# OVC3860_Bluetooth_Receiver.net
KiCad netlist of a schematic drawn in EAGLE
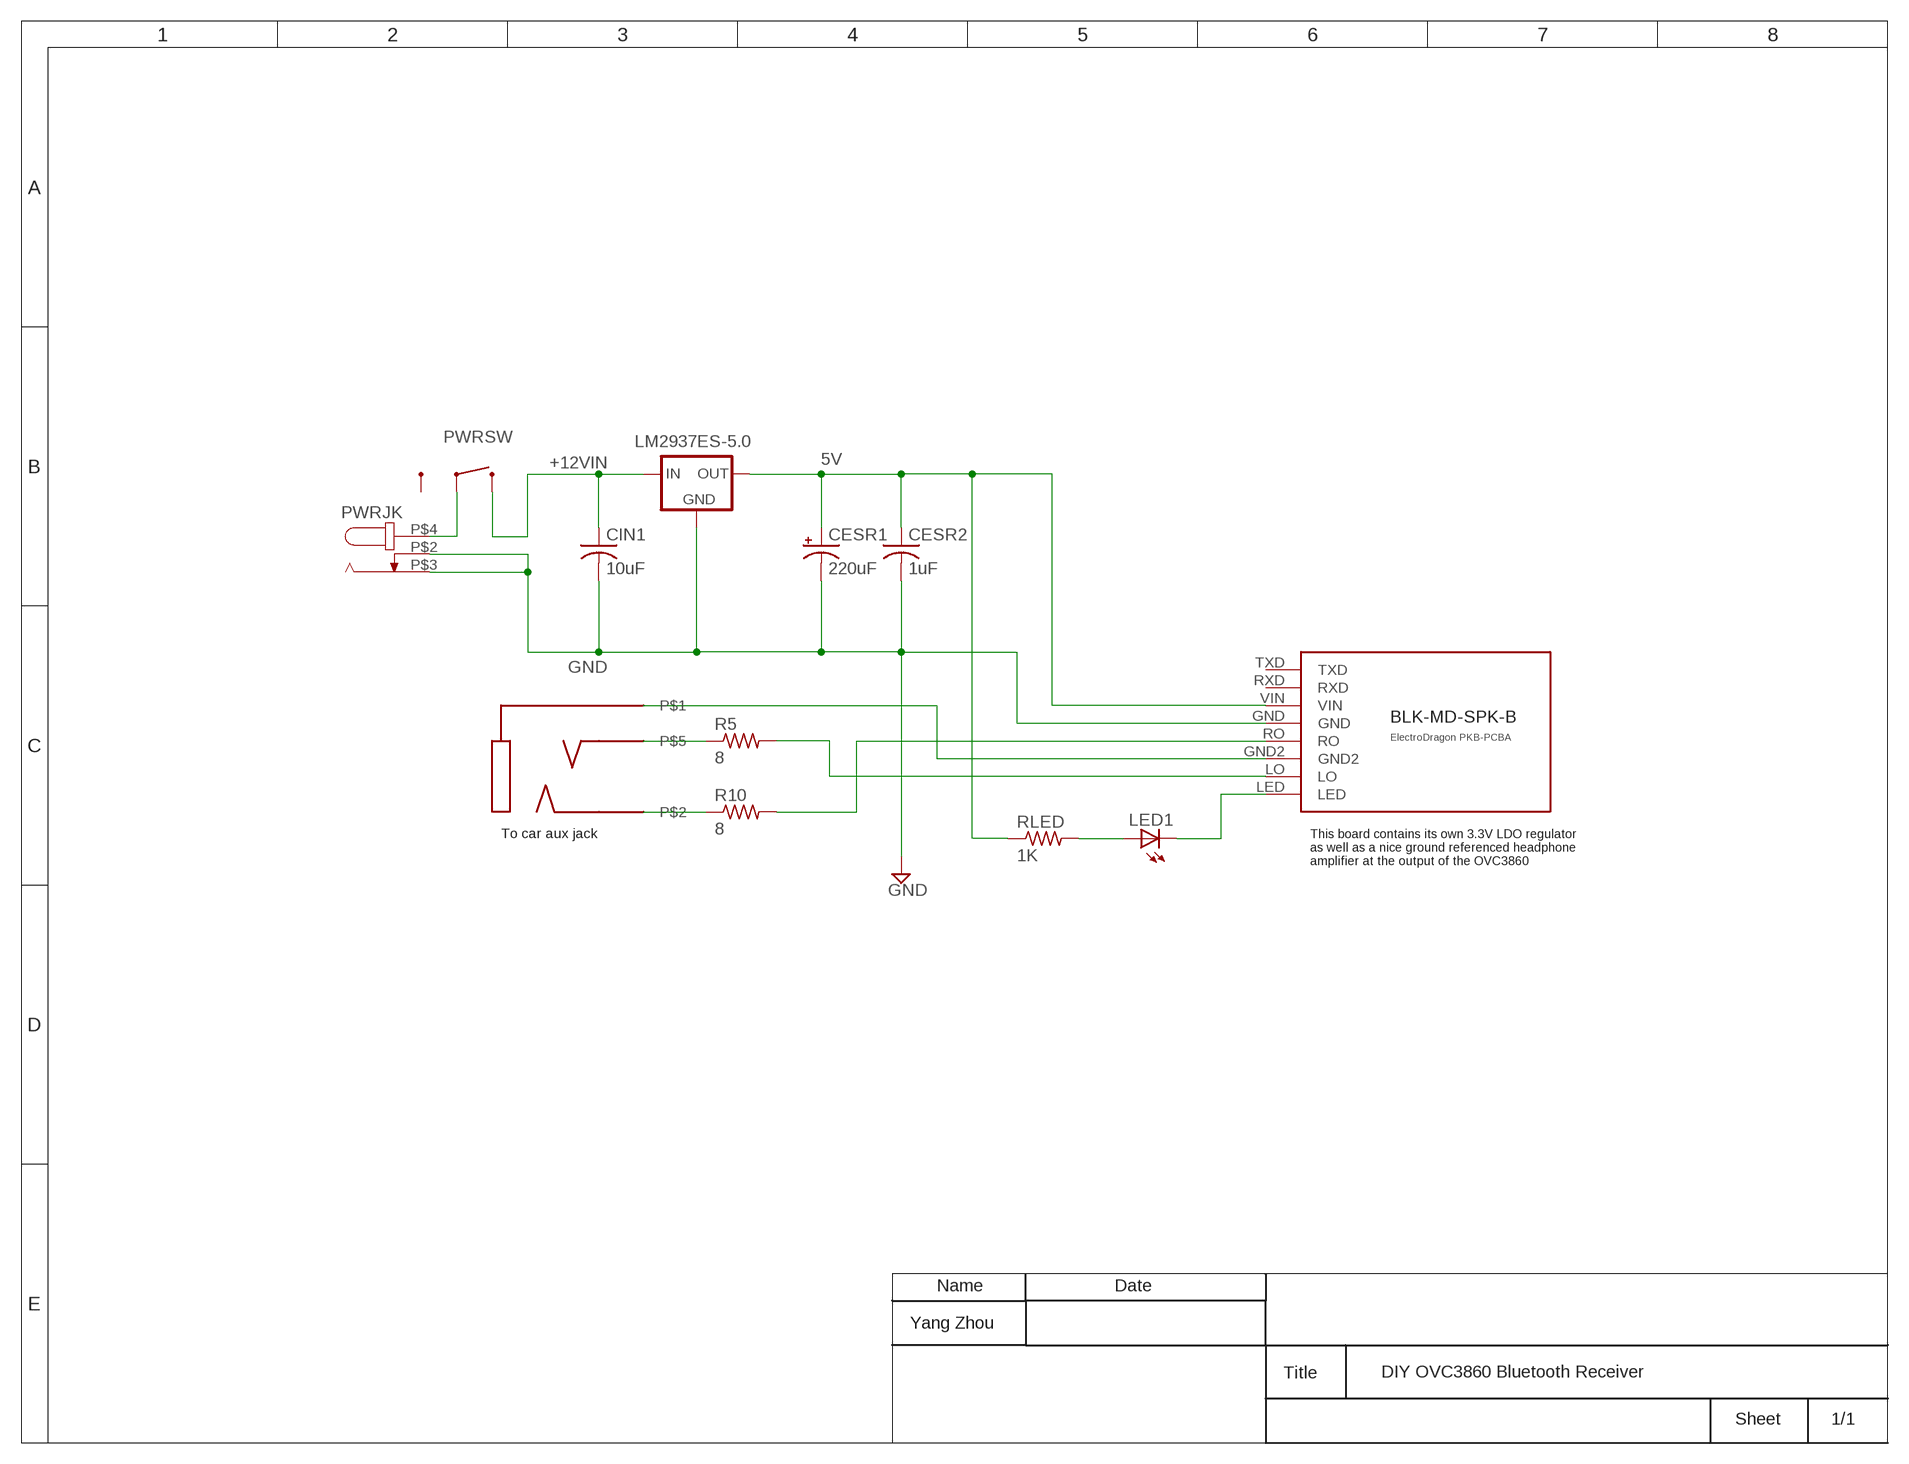
[diagram p0: schematic, sheet 1]

(export (version "E")
  (design (tool "Eeschema 10.0.6"))
  (components
    (comp (ref "CESR1")
      (value "220uF")
      (footprint "eagle-import:E3,5-8")
      (libsource (lib "eagle-import") (part "CPOL-USE3.5-8"))
    )
    (comp (ref "CESR2")
      (value "1uF")
      (footprint "eagle-import:C1206")
      (libsource (lib "eagle-import") (part "C-USC1206"))
    )
    (comp (ref "CIN1")
      (value "10uF")
      (footprint "eagle-import:C1206")
      (libsource (lib "eagle-import") (part "C-USC1206"))
    )
    (comp (ref "LED1")
      (value "LEDCHIPLED_1206")
      (footprint "eagle-import:CHIPLED_1206")
      (libsource (lib "eagle-import") (part "LEDCHIPLED_1206"))
    )
    (comp (ref "LM2937ES-5.0")
      (value "LM340S-5.0")
      (footprint "eagle-import:TO-263-3")
      (libsource (lib "eagle-import") (part "LM340S-5.0"))
    )
    (comp (ref "PWRJK")
      (value "A-4118_DCPOWJACK")
      (footprint "eagle-import:A-4118")
      (libsource (lib "eagle-import") (part "A-4118_DCPOWJACK"))
    )
    (comp (ref "PWRSW")
      (value "103-12100-EV")
      (footprint "eagle-import:103-12100-EV")
      (libsource (lib "eagle-import") (part "103-12100-EV"))
    )
    (comp (ref "R5")
      (value "8")
      (footprint "eagle-import:0207_7")
      (libsource (lib "eagle-import") (part "R-US_0207/7"))
    )
    (comp (ref "R10")
      (value "8")
      (footprint "eagle-import:0207_7")
      (libsource (lib "eagle-import") (part "R-US_0207/7"))
    )
    (comp (ref "RLED")
      (value "1K")
      (footprint "eagle-import:R0805")
      (libsource (lib "eagle-import") (part "R-US_R0805"))
    )
    (comp (ref "U$2")
      (value "STX-3120-3B")
      (footprint "eagle-import:STX-3120-3B")
      (libsource (lib "eagle-import") (part "STX-3120-3B"))
    )
    (comp (ref "U$3")
      (value "PKB-PCBA")
      (footprint "eagle-import:PKB-PCBA")
      (libsource (lib "eagle-import") (part "PKB-PCBA"))
    )
  )
  (nets
    (net (code "1") (name "/+12VIN") (class "Default")
      (node (ref "CIN1") (pin "1") (pinfunction "1_1") (pintype "passive"))
      (node (ref "LM2937ES-5.0") (pin "1") (pinfunction "IN_1") (pintype "input"))
      (node (ref "PWRSW") (pin "3") (pinfunction "3_3") (pintype "passive"))
    )
    (net (code "2") (name "GND") (class "Default")
      (node (ref "CESR1") (pin "-") (pinfunction "-_-") (pintype "passive"))
      (node (ref "CESR2") (pin "2") (pinfunction "2_2") (pintype "passive"))
      (node (ref "CIN1") (pin "2") (pinfunction "2_2") (pintype "passive"))
      (node (ref "LM2937ES-5.0") (pin "2") (pinfunction "GND_2") (pintype "input"))
      (node (ref "LM2937ES-5.0") (pin "GND") (pinfunction "GND_GND") (pintype "input"))
      (node (ref "PWRJK") (pin "P$2") (pinfunction "2_P$2") (pintype "passive"))
      (node (ref "PWRJK") (pin "P$3") (pinfunction "3_P$3") (pintype "passive"))
      (node (ref "U$3") (pin "GND") (pinfunction "GND_GND") (pintype "bidirectional"))
    )
    (net (code "3") (name "Net-(LED1-PadA)") (class "Default")
      (node (ref "LED1") (pin "A") (pinfunction "A_A") (pintype "passive"))
      (node (ref "RLED") (pin "2") (pinfunction "2_2") (pintype "passive"))
    )
    (net (code "4") (name "Net-(LED1-PadC)") (class "Default")
      (node (ref "LED1") (pin "C") (pinfunction "C_C") (pintype "passive"))
      (node (ref "U$3") (pin "LED") (pinfunction "LED_LED") (pintype "bidirectional"))
    )
    (net (code "5") (name "Net-(LM2937ES-5.0-OUT)") (class "Default")
      (node (ref "CESR1") (pin "+") (pinfunction "+_+") (pintype "passive"))
      (node (ref "CESR2") (pin "1") (pinfunction "1_1") (pintype "passive"))
      (node (ref "LM2937ES-5.0") (pin "3") (pinfunction "OUT_3") (pintype "passive"))
      (node (ref "RLED") (pin "1") (pinfunction "1_1") (pintype "passive"))
      (node (ref "U$3") (pin "VIN") (pinfunction "VIN_VIN") (pintype "bidirectional"))
    )
    (net (code "6") (name "Net-(PWRJK-1)") (class "Default")
      (node (ref "PWRJK") (pin "P$4") (pinfunction "1_P$4") (pintype "passive"))
      (node (ref "PWRSW") (pin "2") (pinfunction "2_2") (pintype "passive"))
    )
    (net (code "7") (name "Net-(R5-Pad2)") (class "Default")
      (node (ref "R5") (pin "2") (pinfunction "2_2") (pintype "passive"))
      (node (ref "U$3") (pin "LO") (pinfunction "LO_LO") (pintype "bidirectional"))
    )
    (net (code "8") (name "Net-(R10-Pad2)") (class "Default")
      (node (ref "R10") (pin "2") (pinfunction "2_2") (pintype "passive"))
      (node (ref "U$3") (pin "RO") (pinfunction "RO_RO") (pintype "bidirectional"))
    )
    (net (code "9") (name "Net-(U$2-P$1)") (class "Default")
      (node (ref "U$2") (pin "1") (pinfunction "P$1_1") (pintype "bidirectional"))
      (node (ref "U$3") (pin "GND2") (pinfunction "GND2_GND2") (pintype "bidirectional"))
    )
    (net (code "10") (name "Net-(U$2-P$2)") (class "Default")
      (node (ref "R10") (pin "1") (pinfunction "1_1") (pintype "passive"))
      (node (ref "U$2") (pin "2") (pinfunction "P$2_2") (pintype "bidirectional"))
    )
    (net (code "11") (name "Net-(U$2-P$5)") (class "Default")
      (node (ref "R5") (pin "1") (pinfunction "1_1") (pintype "passive"))
      (node (ref "U$2") (pin "5") (pinfunction "P$5_5") (pintype "bidirectional"))
    )
    (net (code "12") (name "unconnected-(PWRSW-Pad1)") (class "Default")
      (node (ref "PWRSW") (pin "1") (pinfunction "1_1") (pintype "passive"))
    )
    (net (code "13") (name "unconnected-(U$3-PadRXD)") (class "Default")
      (node (ref "U$3") (pin "RXD") (pinfunction "RXD_RXD") (pintype "bidirectional"))
    )
    (net (code "14") (name "unconnected-(U$3-PadTXD)") (class "Default")
      (node (ref "U$3") (pin "TXD") (pinfunction "TXD_TXD") (pintype "bidirectional"))
    )
  )
)
